# power_copy.net
KiCad netlist of a schematic drawn in Altium Designer
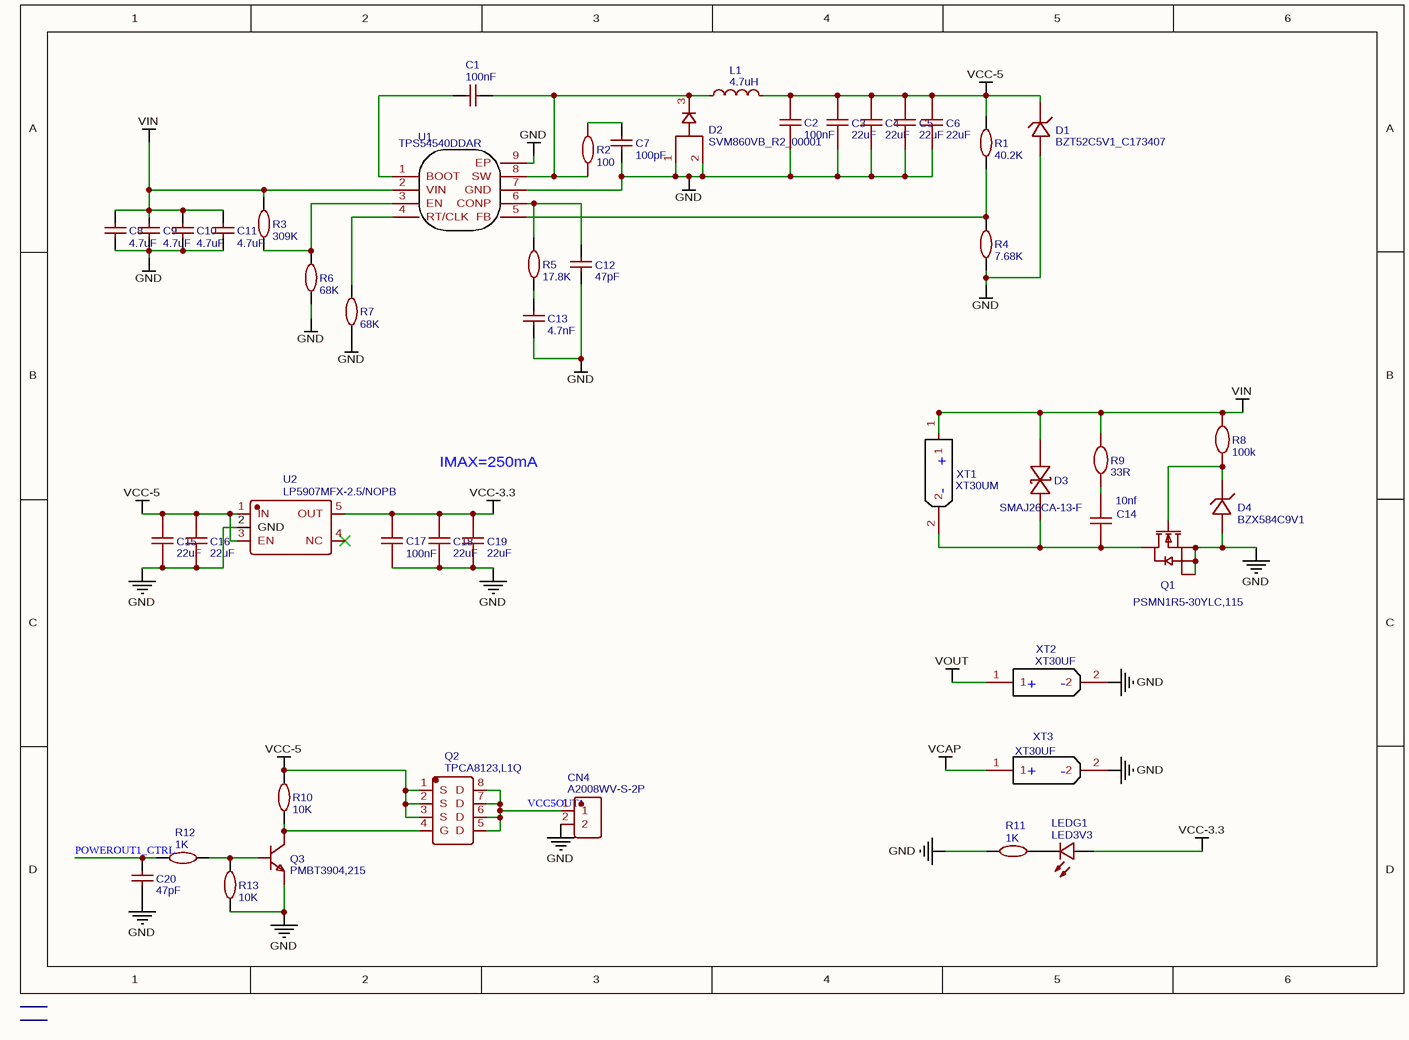
[diagram p0: power copy.SchDoc]

(export (version "E")
  (design (tool "Eeschema 10.0.6"))
  (components
    (comp (ref "C1")
      (value "100nF")
      (footprint "C0603")
      (fields
        (field (name "BOM_MANUFACTURER PART") "CL05B104KO5NNNC")
        (field (name "BOM_SUPPLIER PART") "C1525")
      )
      (libsource (lib "altium-import") (part "root_0_100nF_"))
    )
    (comp (ref "C2")
      (value "100nF")
      (footprint "C0603")
      (fields
        (field (name "BOM_SUPPLIER PART") "C408909")
        (field (name "BOM_MANUFACTURER PART") "AC0603KRX7R0BB104")
        (field (name "CONTRIBUTOR") "LCSC")
      )
      (libsource (lib "altium-import") (part "root_1_100nF_"))
    )
    (comp (ref "C3")
      (value "22uF")
      (footprint "C0603")
      (fields
        (field (name "BOM_MANUFACTURER PART") "CL10A226MQ8NRNC")
        (field (name "BOM_SUPPLIER PART") "C59461")
      )
      (libsource (lib "altium-import") (part "root_1_22uF_"))
    )
    (comp (ref "C4")
      (value "22uF")
      (footprint "C0603")
      (fields
        (field (name "BOM_MANUFACTURER PART") "CL10A226MQ8NRNC")
        (field (name "BOM_SUPPLIER PART") "C59461")
      )
      (libsource (lib "altium-import") (part "root_1_22uF_"))
    )
    (comp (ref "C5")
      (value "22uF")
      (footprint "C0603")
      (fields
        (field (name "BOM_MANUFACTURER PART") "CL10A226MQ8NRNC")
        (field (name "BOM_SUPPLIER PART") "C59461")
      )
      (libsource (lib "altium-import") (part "root_1_22uF_"))
    )
    (comp (ref "C6")
      (value "22uF")
      (footprint "C0603")
      (fields
        (field (name "BOM_MANUFACTURER PART") "CL10A226MQ8NRNC")
        (field (name "BOM_SUPPLIER PART") "C59461")
      )
      (libsource (lib "altium-import") (part "root_1_22uF_"))
    )
    (comp (ref "C7")
      (value "100pF")
      (footprint "C0603")
      (fields
        (field (name "BOM_MANUFACTURER PART") "CGA3E2C0G1H101JT0Y0N")
        (field (name "BOM_SUPPLIER PART") "C76709")
      )
      (libsource (lib "altium-import") (part "root_3_100pF_"))
    )
    (comp (ref "C8")
      (value "4.7uF")
      (footprint "C0805")
      (fields
        (field (name "BOM_MANUFACTURER PART") "CL21A475KBQNNNE")
        (field (name "BOM_SUPPLIER PART") "C98192")
      )
      (libsource (lib "altium-import") (part "root_1_4.7uF_"))
    )
    (comp (ref "C9")
      (value "4.7uF")
      (footprint "C0805")
      (fields
        (field (name "BOM_MANUFACTURER PART") "CL21A475KBQNNNE")
        (field (name "BOM_SUPPLIER PART") "C98192")
      )
      (libsource (lib "altium-import") (part "root_1_4.7uF_"))
    )
    (comp (ref "C10")
      (value "4.7uF")
      (footprint "C0805")
      (fields
        (field (name "BOM_MANUFACTURER PART") "CL21A475KBQNNNE")
        (field (name "BOM_SUPPLIER PART") "C98192")
      )
      (libsource (lib "altium-import") (part "root_1_4.7uF_"))
    )
    (comp (ref "C11")
      (value "4.7uF")
      (footprint "C0805")
      (fields
        (field (name "BOM_MANUFACTURER PART") "CL21A475KBQNNNE")
        (field (name "BOM_SUPPLIER PART") "C98192")
      )
      (libsource (lib "altium-import") (part "root_1_4.7uF_"))
    )
    (comp (ref "C12")
      (value "47pF")
      (footprint "C0402")
      (fields
        (field (name "BOM_MANUFACTURER PART") "0402CG470J500NT")
        (field (name "BOM_SUPPLIER PART") "C1567")
      )
      (libsource (lib "altium-import") (part "root_1_47pF_"))
    )
    (comp (ref "C13")
      (value "4.7nF")
      (footprint "C0402")
      (fields
        (field (name "BOM_MANUFACTURER PART") "0402B472K500NT")
        (field (name "BOM_SUPPLIER PART") "C1538")
      )
      (libsource (lib "altium-import") (part "root_1_4.7nF_"))
    )
    (comp (ref "C14")
      (value "10nf")
      (footprint "C0603")
      (libsource (lib "altium-import") (part "root_0_10nf_"))
    )
    (comp (ref "C15")
      (value "22uF")
      (footprint "C0603")
      (fields
        (field (name "BOM_MANUFACTURER PART") "CL10A226MQ8NRNC")
        (field (name "BOM_SUPPLIER PART") "C59461")
      )
      (libsource (lib "altium-import") (part "root_1_22uF_"))
    )
    (comp (ref "C16")
      (value "22uF")
      (footprint "C0603")
      (fields
        (field (name "BOM_MANUFACTURER PART") "CL10A226MQ8NRNC")
        (field (name "BOM_SUPPLIER PART") "C59461")
      )
      (libsource (lib "altium-import") (part "root_1_22uF_"))
    )
    (comp (ref "C17")
      (value "100nF")
      (footprint "C0402")
      (fields
        (field (name "BOM_MANUFACTURER PART") "GRM188R71H104KA93D")
        (field (name "BOM_SUPPLIER PART") "C77055")
      )
      (libsource (lib "altium-import") (part "root_1_100nF_"))
    )
    (comp (ref "C18")
      (value "22uF")
      (footprint "C0603")
      (fields
        (field (name "BOM_MANUFACTURER PART") "CL10A226MQ8NRNC")
        (field (name "BOM_SUPPLIER PART") "C59461")
      )
      (libsource (lib "altium-import") (part "root_1_22uF_"))
    )
    (comp (ref "C19")
      (value "22uF")
      (footprint "C0603")
      (fields
        (field (name "BOM_MANUFACTURER PART") "CL10A226MQ8NRNC")
        (field (name "BOM_SUPPLIER PART") "C59461")
      )
      (libsource (lib "altium-import") (part "root_1_22uF_"))
    )
    (comp (ref "C20")
      (value "47pF")
      (footprint "C0402")
      (fields
        (field (name "BOM_MANUFACTURER PART") "0402CG470J500NT")
        (field (name "BOM_SUPPLIER PART") "C1567")
      )
      (libsource (lib "altium-import") (part "root_1_47pF_"))
    )
    (comp (ref "CN4")
      (value "A2008WV-S-2P")
      (footprint "CONN-SMD_A2008WV-S-2P")
      (fields (field (name "BOM_SUPPLIER PART") "C273123") (field (name "CONTRIBUTOR") "LCSC"))
      (libsource (lib "altium-import") (part "root_0_A2008WV-S-2P_"))
    )
    (comp (ref "D1")
      (value "BZT52C5V1_C173407")
      (footprint "SOD-123_L2.7-W1.6-LS3.7-RD")
      (fields
        (field (name "BOM_SUPPLIER PART") "C173407")
        (field (name "BOM_MANUFACTURER PART") "BZT52C5V1")
        (field (name "CONTRIBUTOR") "LCSC")
      )
      (libsource (lib "altium-import") (part "root_3_BZT52C5V1_C173407_"))
    )
    (comp (ref "D2")
      (value "SVM860VB_R2_00001")
      (footprint "TO-277B_3P-L6.1-W4.3-LS7.0-BR")
      (fields (field (name "BOM_SUPPLIER PART") "C391734") (field (name "CONTRIBUTOR") "LCSC"))
      (libsource (lib "altium-import") (part "root_3_SVM860VB_R2_00001_"))
    )
    (comp (ref "D3")
      (value "SMAJ26CA-13-F")
      (footprint "SMA_L4.4-W2.6-LS5.0-BI")
      (fields (field (name "BOM_SUPPLIER PART") "C134976") (field (name "CONTRIBUTOR") "LCSC"))
      (libsource (lib "altium-import") (part "root_1_SMAJ26CA-13-F_"))
    )
    (comp (ref "D4")
      (value "BZX584C9V1")
      (footprint "SOD-523F_L1.7-W0.9-LS1.7-RD")
      (libsource (lib "altium-import") (part "root_3_BZX584C9V1_"))
    )
    (comp (ref "L1")
      (value "4.7uH")
      (footprint "IND-SMD_L6.0-W6.0")
      (fields
        (field (name "BOM_SUPPLIER PART") "C266428")
        (field (name "BOM_MANUFACTURER PART") "SMNR6028-4R7MT")
        (field (name "CONTRIBUTOR") "LCSC")
      )
      (libsource (lib "altium-import") (part "root_0_4.7uH_"))
    )
    (comp (ref "LEDG1")
      (value "LED3V3")
      (footprint "LED-0603")
      (fields
        (field (name "BOM_MANUFACTURER PART") "19-217/GHC-YR1S2/3T")
        (field (name "BOM_SUPPLIER PART") "C72043")
      )
      (libsource (lib "altium-import") (part "root_2_LED3V3_"))
    )
    (comp (ref "Q1")
      (value "PSMN1R5-30YLC,115")
      (footprint "SOT-669_L4.9-W4.0-P1.27-LS6.0-BR")
      (fields (field (name "BOM_SUPPLIER PART") "C427523") (field (name "CONTRIBUTOR") "LCSC"))
      (libsource (lib "altium-import") (part "root_3_PSMN1R5-30YLC,115_"))
    )
    (comp (ref "Q2")
      (value "TPCA8123,L1Q")
      (footprint "POWERVDFN-8_L6.0-W5.0-P1.27-BL")
      (fields (field (name "BOM_SUPPLIER PART") "C180399") (field (name "CONTRIBUTOR") "LCSC"))
      (libsource (lib "altium-import") (part "root_0_TPCA8123,L1Q_"))
    )
    (comp (ref "Q3")
      (value "PMBT3904,215")
      (footprint "SOT-23_L2.9-W1.3-P0.95-LS2.4-BR")
      (fields (field (name "BOM_SUPPLIER PART") "C8667"))
      (libsource (lib "altium-import") (part "root_0_PMBT3904,215_"))
    )
    (comp (ref "R1")
      (value "40.2K")
      (footprint "R0603")
      (fields
        (field (name "BOM_MANUFACTURER PART") "0603WAF4022T5E")
        (field (name "BOM_SUPPLIER PART") "C12447")
      )
      (libsource (lib "altium-import") (part "root_1_40.2K_"))
    )
    (comp (ref "R2")
      (value "100")
      (footprint "R0402")
      (fields
        (field (name "BOM_SUPPLIER PART") "C144808")
        (field (name "BOM_MANUFACTURER PART") "AC0402FR-07100RL")
        (field (name "CONTRIBUTOR") "LCSC")
      )
      (libsource (lib "altium-import") (part "root_1_100_"))
    )
    (comp (ref "R3")
      (value "309K")
      (footprint "R0603")
      (fields
        (field (name "BOM_MANUFACTURER PART") "0603WAF3093T5E")
        (field (name "BOM_SUPPLIER PART") "C23001")
      )
      (libsource (lib "altium-import") (part "root_1_309K_"))
    )
    (comp (ref "R4")
      (value "7.68K")
      (footprint "R0402")
      (fields
        (field (name "BOM_MANUFACTURER PART") "0402WGF7681TCE")
        (field (name "BOM_SUPPLIER PART") "C25919")
      )
      (libsource (lib "altium-import") (part "root_1_7.68K_"))
    )
    (comp (ref "R5")
      (value "17.8K")
      (footprint "R0603")
      (fields
        (field (name "BOM_MANUFACTURER PART") "0603WAF1782T5E")
        (field (name "BOM_SUPPLIER PART") "C22821")
      )
      (libsource (lib "altium-import") (part "root_1_17.8K_"))
    )
    (comp (ref "R6")
      (value "68K")
      (footprint "R0603")
      (fields
        (field (name "BOM_MANUFACTURER PART") "0603WAF6802T5E")
        (field (name "BOM_SUPPLIER PART") "C23231")
      )
      (libsource (lib "altium-import") (part "root_1_68K_"))
    )
    (comp (ref "R7")
      (value "68K")
      (footprint "R0603")
      (fields
        (field (name "BOM_MANUFACTURER PART") "0603WAF6802T5E")
        (field (name "BOM_SUPPLIER PART") "C23231")
      )
      (libsource (lib "altium-import") (part "root_1_68K_"))
    )
    (comp (ref "R8")
      (value "100k")
      (footprint "R0603")
      (libsource (lib "altium-import") (part "root_1_100k_"))
    )
    (comp (ref "R9") (value "33R") (footprint "R0603") (libsource (lib "altium-import") (part "root_1_33R_")))
    (comp (ref "R10")
      (value "10K")
      (footprint "R0402")
      (fields
        (field (name "BOM_MANUFACTURER PART") "0402WGF1002TCE")
        (field (name "BOM_SUPPLIER PART") "C25744")
      )
      (libsource (lib "altium-import") (part "root_1_10K_"))
    )
    (comp (ref "R11")
      (value "1K")
      (footprint "R0603")
      (fields
        (field (name "BOM_MANUFACTURER PART") "0402WGF1001TCE")
        (field (name "BOM_SUPPLIER PART") "C11702")
      )
      (libsource (lib "altium-import") (part "root_0_1K_"))
    )
    (comp (ref "R12")
      (value "1K")
      (footprint "R0402")
      (fields
        (field (name "BOM_MANUFACTURER PART") "0402WGF1001TCE")
        (field (name "BOM_SUPPLIER PART") "C11702")
      )
      (libsource (lib "altium-import") (part "root_0_1K_"))
    )
    (comp (ref "R13")
      (value "10K")
      (footprint "R0402")
      (fields
        (field (name "BOM_MANUFACTURER PART") "0402WGF1002TCE")
        (field (name "BOM_SUPPLIER PART") "C25744")
      )
      (libsource (lib "altium-import") (part "root_1_10K_"))
    )
    (comp (ref "U1")
      (value "TPS54540DDAR")
      (footprint "SOIC-8_L4.9-W3.9-P1.27-LS6.0-BL-EP")
      (fields (field (name "BOM_SUPPLIER PART") "C95286"))
      (libsource (lib "altium-import") (part "root_0_TPS54540DDAR_"))
    )
    (comp (ref "U2")
      (value "LP5907MFX-2.5/NOPB")
      (footprint "SOT-23-5_L3.0-W1.7-P0.95-LS2.8-BL")
      (fields (field (name "BOM_SUPPLIER PART") "C165132") (field (name "CONTRIBUTOR") "LCSC"))
      (libsource (lib "altium-import") (part "root_0_LP5907MFX-2.5/NOPB_"))
    )
    (comp (ref "XT1")
      (value "XT30UM")
      (footprint "CONN-TH_XT30UPB-F")
      (fields (field (name "BOM_MANUFACTURER PART") "XT60") (field (name "CONTRIBUTOR") "4bucks"))
      (libsource (lib "altium-import") (part "root_3_XT30UM_"))
    )
    (comp (ref "XT2")
      (value "XT30UF")
      (footprint "CONN-TH_XT30UPB-F")
      (fields (field (name "BOM_MANUFACTURER PART") "XT60") (field (name "CONTRIBUTOR") "4bucks"))
      (libsource (lib "altium-import") (part "root_0_XT30UF_"))
    )
    (comp (ref "XT3")
      (value "XT30UF")
      (footprint "CONN-TH_XT30UPB-F")
      (fields (field (name "BOM_MANUFACTURER PART") "XT60") (field (name "CONTRIBUTOR") "4bucks"))
      (libsource (lib "altium-import") (part "root_0_XT30UF_"))
    )
  )
  (nets
    (net (code "1") (name "/POWEROUT1_CTRL") (class "Default")
      (node (ref "C20") (pin "2") (pinfunction "2_2") (pintype "passive"))
      (node (ref "R12") (pin "1") (pinfunction "1_1") (pintype "passive"))
    )
    (net (code "2") (name "/VCC5OUT1") (class "Default")
      (node (ref "CN4") (pin "1") (pinfunction "1_1") (pintype "passive"))
      (node (ref "Q2") (pin "5") (pinfunction "D_5") (pintype "passive"))
      (node (ref "Q2") (pin "6") (pinfunction "D_6") (pintype "passive"))
      (node (ref "Q2") (pin "7") (pinfunction "D_7") (pintype "passive"))
      (node (ref "Q2") (pin "8") (pinfunction "D_8") (pintype "passive"))
    )
    (net (code "3") (name "GND") (class "Default")
      (node (ref "C10") (pin "1") (pinfunction "1_1") (pintype "passive"))
      (node (ref "C11") (pin "1") (pinfunction "1_1") (pintype "passive"))
      (node (ref "C12") (pin "1") (pinfunction "1_1") (pintype "passive"))
      (node (ref "C13") (pin "1") (pinfunction "1_1") (pintype "passive"))
      (node (ref "C15") (pin "1") (pinfunction "1_1") (pintype "passive"))
      (node (ref "C16") (pin "1") (pinfunction "1_1") (pintype "passive"))
      (node (ref "C17") (pin "1") (pinfunction "1_1") (pintype "passive"))
      (node (ref "C18") (pin "1") (pinfunction "1_1") (pintype "passive"))
      (node (ref "C19") (pin "1") (pinfunction "1_1") (pintype "passive"))
      (node (ref "C2") (pin "1") (pinfunction "1_1") (pintype "passive"))
      (node (ref "C20") (pin "1") (pinfunction "1_1") (pintype "passive"))
      (node (ref "C3") (pin "1") (pinfunction "1_1") (pintype "passive"))
      (node (ref "C4") (pin "1") (pinfunction "1_1") (pintype "passive"))
      (node (ref "C5") (pin "1") (pinfunction "1_1") (pintype "passive"))
      (node (ref "C6") (pin "1") (pinfunction "1_1") (pintype "passive"))
      (node (ref "C7") (pin "2") (pinfunction "2_2") (pintype "passive"))
      (node (ref "C8") (pin "1") (pinfunction "1_1") (pintype "passive"))
      (node (ref "C9") (pin "1") (pinfunction "1_1") (pintype "passive"))
      (node (ref "CN4") (pin "2") (pinfunction "2_2") (pintype "passive"))
      (node (ref "D1") (pin "2") (pinfunction "A_2") (pintype "passive"))
      (node (ref "D2") (pin "1") (pinfunction "1_1") (pintype "passive"))
      (node (ref "D2") (pin "2") (pinfunction "2_2") (pintype "passive"))
      (node (ref "D4") (pin "2") (pinfunction "A_2") (pintype "passive"))
      (node (ref "Q1") (pin "1") (pinfunction "S_1") (pintype "passive"))
      (node (ref "Q1") (pin "2") (pinfunction "S_2") (pintype "passive"))
      (node (ref "Q1") (pin "3") (pinfunction "S_3") (pintype "passive"))
      (node (ref "Q3") (pin "2") (pinfunction "2_2") (pintype "passive"))
      (node (ref "R11") (pin "1") (pinfunction "1_1") (pintype "passive"))
      (node (ref "R13") (pin "1") (pinfunction "1_1") (pintype "passive"))
      (node (ref "R4") (pin "1") (pinfunction "1_1") (pintype "passive"))
      (node (ref "R6") (pin "1") (pinfunction "1_1") (pintype "passive"))
      (node (ref "R7") (pin "1") (pinfunction "1_1") (pintype "passive"))
      (node (ref "U1") (pin "7") (pinfunction "GND_7") (pintype "passive"))
      (node (ref "U1") (pin "9") (pinfunction "EP_9") (pintype "passive"))
      (node (ref "U2") (pin "2") (pinfunction "GND_2") (pintype "passive"))
      (node (ref "XT2") (pin "2") (pinfunction "2_2") (pintype "passive"))
      (node (ref "XT3") (pin "2") (pinfunction "2_2") (pintype "passive"))
    )
    (net (code "4") (name "Net-(C7-Pad1)") (class "Default")
      (node (ref "C7") (pin "1") (pinfunction "1_1") (pintype "passive"))
      (node (ref "R2") (pin "2") (pinfunction "2_2") (pintype "passive"))
    )
    (net (code "5") (name "Net-(C13-Pad2)") (class "Default")
      (node (ref "C13") (pin "2") (pinfunction "2_2") (pintype "passive"))
      (node (ref "R5") (pin "1") (pinfunction "1_1") (pintype "passive"))
    )
    (net (code "6") (name "Net-(C14-Pad2)") (class "Default")
      (node (ref "C14") (pin "2") (pinfunction "2_2") (pintype "passive"))
      (node (ref "R9") (pin "1") (pinfunction "1_1") (pintype "passive"))
    )
    (net (code "7") (name "Net-(D4-K)") (class "Default")
      (node (ref "D4") (pin "1") (pinfunction "K_1") (pintype "passive"))
      (node (ref "Q1") (pin "4") (pinfunction "G_4") (pintype "passive"))
      (node (ref "R8") (pin "1") (pinfunction "1_1") (pintype "passive"))
    )
    (net (code "8") (name "Net-(LEDG1-C)") (class "Default")
      (node (ref "LEDG1") (pin "2") (pinfunction "C_2") (pintype "passive"))
      (node (ref "R11") (pin "2") (pinfunction "2_2") (pintype "passive"))
    )
    (net (code "9") (name "Net-(Q1-D)") (class "Default")
      (node (ref "C14") (pin "1") (pinfunction "1_1") (pintype "passive"))
      (node (ref "D3") (pin "1") (pinfunction "1_1") (pintype "passive"))
      (node (ref "Q1") (pin "5") (pinfunction "D_5") (pintype "passive"))
      (node (ref "XT1") (pin "2") (pinfunction "2_2") (pintype "passive"))
    )
    (net (code "10") (name "Net-(Q2-G)") (class "Default")
      (node (ref "Q2") (pin "4") (pinfunction "G_4") (pintype "passive"))
      (node (ref "Q3") (pin "3") (pinfunction "3_3") (pintype "passive"))
      (node (ref "R10") (pin "1") (pinfunction "1_1") (pintype "passive"))
    )
    (net (code "11") (name "Net-(Q3-Pad1)") (class "Default")
      (node (ref "Q3") (pin "1") (pinfunction "1_1") (pintype "passive"))
      (node (ref "R12") (pin "2") (pinfunction "2_2") (pintype "passive"))
      (node (ref "R13") (pin "2") (pinfunction "2_2") (pintype "passive"))
    )
    (net (code "12") (name "Net-(U1-BOOT)") (class "Default")
      (node (ref "C1") (pin "1") (pinfunction "1_1") (pintype "passive"))
      (node (ref "U1") (pin "1") (pinfunction "BOOT_1") (pintype "passive"))
    )
    (net (code "13") (name "Net-(U1-CONP)") (class "Default")
      (node (ref "C12") (pin "2") (pinfunction "2_2") (pintype "passive"))
      (node (ref "R5") (pin "2") (pinfunction "2_2") (pintype "passive"))
      (node (ref "U1") (pin "6") (pinfunction "CONP_6") (pintype "passive"))
    )
    (net (code "14") (name "Net-(U1-EN)") (class "Default")
      (node (ref "R3") (pin "1") (pinfunction "1_1") (pintype "passive"))
      (node (ref "R6") (pin "2") (pinfunction "2_2") (pintype "passive"))
      (node (ref "U1") (pin "3") (pinfunction "EN_3") (pintype "passive"))
    )
    (net (code "15") (name "Net-(U1-FB)") (class "Default")
      (node (ref "R1") (pin "1") (pinfunction "1_1") (pintype "passive"))
      (node (ref "R4") (pin "2") (pinfunction "2_2") (pintype "passive"))
      (node (ref "U1") (pin "5") (pinfunction "FB_5") (pintype "passive"))
    )
    (net (code "16") (name "Net-(U1-RT{slash}CLK)") (class "Default")
      (node (ref "R7") (pin "2") (pinfunction "2_2") (pintype "passive"))
      (node (ref "U1") (pin "4") (pinfunction "RT/CLK_4") (pintype "passive"))
    )
    (net (code "17") (name "Net-(U1-SW)") (class "Default")
      (node (ref "C1") (pin "2") (pinfunction "2_2") (pintype "passive"))
      (node (ref "D2") (pin "3") (pinfunction "3_3") (pintype "passive"))
      (node (ref "L1") (pin "1") (pinfunction "1_1") (pintype "passive"))
      (node (ref "R2") (pin "1") (pinfunction "1_1") (pintype "passive"))
      (node (ref "U1") (pin "8") (pinfunction "SW_8") (pintype "passive"))
    )
    (net (code "18") (name "VCAP") (class "Default")
      (node (ref "XT3") (pin "1") (pinfunction "1_1") (pintype "passive"))
    )
    (net (code "19") (name "VCC-3.3") (class "Default")
      (node (ref "C17") (pin "2") (pinfunction "2_2") (pintype "passive"))
      (node (ref "C18") (pin "2") (pinfunction "2_2") (pintype "passive"))
      (node (ref "C19") (pin "2") (pinfunction "2_2") (pintype "passive"))
      (node (ref "LEDG1") (pin "1") (pinfunction "A_1") (pintype "passive"))
      (node (ref "U2") (pin "5") (pinfunction "OUT_5") (pintype "passive"))
    )
    (net (code "20") (name "VCC-5") (class "Default")
      (node (ref "C15") (pin "2") (pinfunction "2_2") (pintype "passive"))
      (node (ref "C16") (pin "2") (pinfunction "2_2") (pintype "passive"))
      (node (ref "C2") (pin "2") (pinfunction "2_2") (pintype "passive"))
      (node (ref "C3") (pin "2") (pinfunction "2_2") (pintype "passive"))
      (node (ref "C4") (pin "2") (pinfunction "2_2") (pintype "passive"))
      (node (ref "C5") (pin "2") (pinfunction "2_2") (pintype "passive"))
      (node (ref "C6") (pin "2") (pinfunction "2_2") (pintype "passive"))
      (node (ref "D1") (pin "1") (pinfunction "C_1") (pintype "passive"))
      (node (ref "L1") (pin "2") (pinfunction "2_2") (pintype "passive"))
      (node (ref "Q2") (pin "1") (pinfunction "S_1") (pintype "passive"))
      (node (ref "Q2") (pin "2") (pinfunction "S_2") (pintype "passive"))
      (node (ref "Q2") (pin "3") (pinfunction "S_3") (pintype "passive"))
      (node (ref "R1") (pin "2") (pinfunction "2_2") (pintype "passive"))
      (node (ref "R10") (pin "2") (pinfunction "2_2") (pintype "passive"))
      (node (ref "U2") (pin "1") (pinfunction "IN_1") (pintype "passive"))
      (node (ref "U2") (pin "3") (pinfunction "EN_3") (pintype "passive"))
    )
    (net (code "21") (name "VIN") (class "Default")
      (node (ref "C10") (pin "2") (pinfunction "2_2") (pintype "passive"))
      (node (ref "C11") (pin "2") (pinfunction "2_2") (pintype "passive"))
      (node (ref "C8") (pin "2") (pinfunction "2_2") (pintype "passive"))
      (node (ref "C9") (pin "2") (pinfunction "2_2") (pintype "passive"))
      (node (ref "D3") (pin "2") (pinfunction "2_2") (pintype "passive"))
      (node (ref "R3") (pin "2") (pinfunction "2_2") (pintype "passive"))
      (node (ref "R8") (pin "2") (pinfunction "2_2") (pintype "passive"))
      (node (ref "R9") (pin "2") (pinfunction "2_2") (pintype "passive"))
      (node (ref "U1") (pin "2") (pinfunction "VIN_2") (pintype "passive"))
      (node (ref "XT1") (pin "1") (pinfunction "1_1") (pintype "passive"))
    )
    (net (code "22") (name "VOUT") (class "Default")
      (node (ref "XT2") (pin "1") (pinfunction "1_1") (pintype "passive"))
    )
    (net (code "23") (name "unconnected-(U2-NC-Pad4)") (class "Default")
      (node (ref "U2") (pin "4") (pinfunction "NC_4") (pintype "passive+no_connect"))
    )
  )
)
